# discharge.net
KiCad netlist of a schematic drawn in Altium Designer
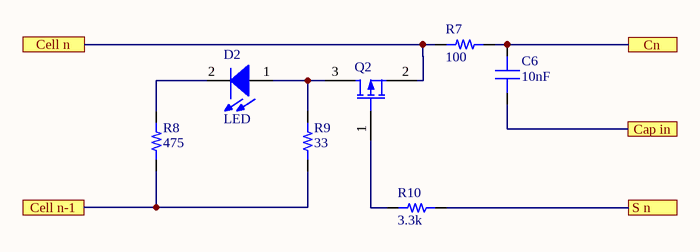
[diagram p0: discharge.SchDoc]

(export (version "E")
  (design (tool "Eeschema 10.0.6"))
  (components
    (comp (ref "C6")
      (value "capacitor")
      (footprint "0603")
      (description "Generic 0603 capacitor")
      (fields (field (name "CAPACITANCE") "10nF") (field (name "VOLTAGE") "50"))
      (libsource (lib "altlib") (part "capacitor"))
    )
    (comp (ref "D2")
      (value "LED")
      (footprint "0805_LED")
      (description "Generic 0805 LED")
      (libsource (lib "altlib") (part "LED"))
    )
    (comp (ref "Q2")
      (value "CMUDM8005 TR PFET")
      (footprint "CMUDM8005 TR SOT523")
      (description "MOSFET P-CH 20V 650MA SOT523")
      (libsource (lib "altlib") (part "CMUDM8005 TR PFET"))
    )
    (comp (ref "R7")
      (value "100")
      (footprint "RES 0603/1608")
      (fields (field (name "RESISTANCE") "100"))
      (libsource (lib "altlib") (part "Resistor"))
    )
    (comp (ref "R8")
      (value "475")
      (footprint "RES 0603/1608")
      (fields (field (name "RESISTANCE") "475"))
      (libsource (lib "altlib") (part "Resistor"))
    )
    (comp (ref "R9")
      (value "33")
      (footprint "RES 2512/6332")
      (fields (field (name "RESISTANCE") "33") (field (name "CREATEDBY") "Kevin"))
      (libsource (lib "altlib") (part "Resistor"))
    )
    (comp (ref "R10")
      (value "3.3k")
      (footprint "RES 0603/1608")
      (fields (field (name "RESISTANCE") "3.3k"))
      (libsource (lib "altlib") (part "Resistor"))
    )
  )
  (nets
    (net (code "1") (name "/Cap in") (class "Default")
      (node (ref "C6") (pin "1") (pinfunction "1_1") (pintype "passive"))
    )
    (net (code "2") (name "/Cell n") (class "Default")
      (node (ref "Q2") (pin "2") (pinfunction "S_2") (pintype "passive"))
      (node (ref "R7") (pin "1") (pinfunction "1_1") (pintype "passive"))
    )
    (net (code "3") (name "/Cell n-1") (class "Default")
      (node (ref "R8") (pin "1") (pinfunction "1_1") (pintype "passive"))
      (node (ref "R9") (pin "1") (pinfunction "1_1") (pintype "passive"))
    )
    (net (code "4") (name "/Cn") (class "Default")
      (node (ref "C6") (pin "2") (pinfunction "2_2") (pintype "passive"))
      (node (ref "R7") (pin "2") (pinfunction "2_2") (pintype "passive"))
    )
    (net (code "5") (name "/S n") (class "Default")
      (node (ref "R10") (pin "2") (pinfunction "2_2") (pintype "passive"))
    )
    (net (code "6") (name "Net-(D2-A)") (class "Default")
      (node (ref "D2") (pin "1") (pinfunction "A_1") (pintype "passive"))
      (node (ref "Q2") (pin "3") (pinfunction "D_3") (pintype "passive"))
      (node (ref "R9") (pin "2") (pinfunction "2_2") (pintype "passive"))
    )
    (net (code "7") (name "Net-(D2-K)") (class "Default")
      (node (ref "D2") (pin "2") (pinfunction "K_2") (pintype "passive"))
      (node (ref "R8") (pin "2") (pinfunction "2_2") (pintype "passive"))
    )
    (net (code "8") (name "Net-(Q2-G)") (class "Default")
      (node (ref "Q2") (pin "1") (pinfunction "G_1") (pintype "passive"))
      (node (ref "R10") (pin "1") (pinfunction "1_1") (pintype "passive"))
    )
  )
)
